# IMU_Section.net
KiCad netlist of a schematic drawn in Altium Designer
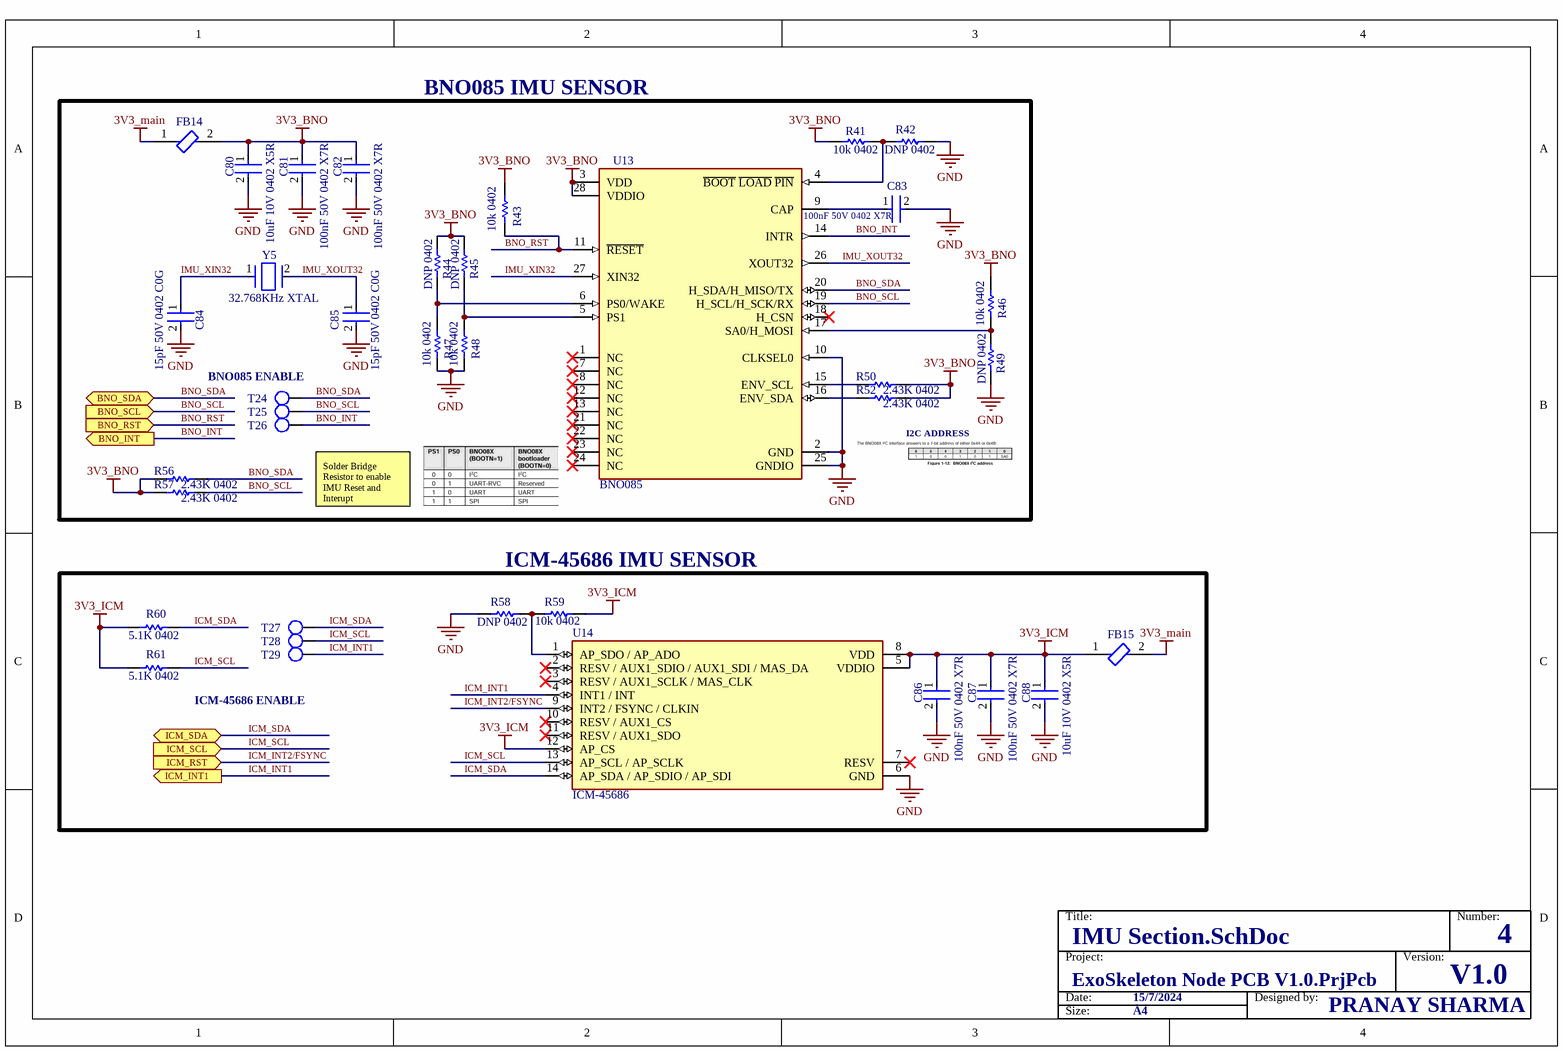
[diagram p0: IMU Section.SchDoc]

(export (version "E")
  (design (tool "Eeschema 10.0.6"))
  (components
    (comp (ref "C80")
      (value "10uF 10V 0402 X5R")
      (footprint "Res, Cap, Ind, LED, FB_Lib:0402 IPC CLASS C CAPACITOR")
      (libsource (lib "Capacitor_Lib") (part "10uF 10V 0402 X5R"))
    )
    (comp (ref "C81")
      (value "100nF 50V 0402 X7R")
      (footprint "Res, Cap, Ind, LED, FB_Lib:0402 IPC CLASS C CAPACITOR")
      (libsource (lib "Capacitor_Lib") (part "100nF 50V 0402 X7R"))
    )
    (comp (ref "C82")
      (value "100nF 50V 0402 X7R")
      (footprint "Res, Cap, Ind, LED, FB_Lib:0402 IPC CLASS C CAPACITOR")
      (libsource (lib "Capacitor_Lib") (part "100nF 50V 0402 X7R"))
    )
    (comp (ref "C83")
      (value "100nF 50V 0402 X7R")
      (footprint "Res, Cap, Ind, LED, FB_Lib:0402 IPC CLASS C CAPACITOR")
      (libsource (lib "Capacitor_Lib") (part "100nF 50V 0402 X7R"))
    )
    (comp (ref "C84")
      (value "15pF 50V 0402 C0G")
      (footprint "Res, Cap, Ind, LED, FB_Lib:0402 IPC CLASS C CAPACITOR")
      (libsource (lib "Capacitor_Lib") (part "15pF 50V 0402 C0G"))
    )
    (comp (ref "C85")
      (value "15pF 50V 0402 C0G")
      (footprint "Res, Cap, Ind, LED, FB_Lib:0402 IPC CLASS C CAPACITOR")
      (libsource (lib "Capacitor_Lib") (part "15pF 50V 0402 C0G"))
    )
    (comp (ref "C86")
      (value "100nF 50V 0402 X7R")
      (footprint "Res, Cap, Ind, LED, FB_Lib:0402 IPC CLASS C CAPACITOR")
      (libsource (lib "Capacitor_Lib") (part "100nF 50V 0402 X7R"))
    )
    (comp (ref "C87")
      (value "100nF 50V 0402 X7R")
      (footprint "Res, Cap, Ind, LED, FB_Lib:0402 IPC CLASS C CAPACITOR")
      (libsource (lib "Capacitor_Lib") (part "100nF 50V 0402 X7R"))
    )
    (comp (ref "C88")
      (value "10uF 10V 0402 X5R")
      (footprint "Res, Cap, Ind, LED, FB_Lib:0402 IPC CLASS C CAPACITOR")
      (libsource (lib "Capacitor_Lib") (part "10uF 10V 0402 X5R"))
    )
    (comp (ref "FB14")
      (value "BLM15AX102SN1D")
      (footprint "Res, Cap, Ind, LED, FB_Lib:0402 IPC CLASS C FERRITE BEAD")
      (libsource (lib "Ferrite_Bead_Lib") (part "BLM15AX102SN1D"))
    )
    (comp (ref "FB15")
      (value "BLM15AX102SN1D")
      (footprint "Res, Cap, Ind, LED, FB_Lib:0402 IPC CLASS C FERRITE BEAD")
      (libsource (lib "Ferrite_Bead_Lib") (part "BLM15AX102SN1D"))
    )
    (comp (ref "R41")
      (value "10k 0402")
      (footprint "Res, Cap, Ind, LED, FB_Lib:0402 IPC CLASS C RESISTOR")
      (libsource (lib "Resistor_Lib") (part "10k 1% 0402"))
    )
    (comp (ref "R42")
      (value "DNP 0402")
      (footprint "Res, Cap, Ind, LED, FB_Lib:0402 IPC CLASS C RESISTOR")
      (libsource (lib "Resistor_Lib") (part "0R 1% 0402"))
    )
    (comp (ref "R43")
      (value "10k 0402")
      (footprint "Res, Cap, Ind, LED, FB_Lib:0402 IPC CLASS C RESISTOR")
      (libsource (lib "Resistor_Lib") (part "10k 1% 0402"))
    )
    (comp (ref "R44")
      (value "DNP 0402")
      (footprint "Res, Cap, Ind, LED, FB_Lib:0402 IPC CLASS C RESISTOR")
      (libsource (lib "Resistor_Lib") (part "0R 1% 0402"))
    )
    (comp (ref "R45")
      (value "DNP 0402")
      (footprint "Res, Cap, Ind, LED, FB_Lib:0402 IPC CLASS C RESISTOR")
      (libsource (lib "Resistor_Lib") (part "0R 1% 0402"))
    )
    (comp (ref "R46")
      (value "10k 0402")
      (footprint "Res, Cap, Ind, LED, FB_Lib:0402 IPC CLASS C RESISTOR")
      (libsource (lib "Resistor_Lib") (part "10k 1% 0402"))
    )
    (comp (ref "R47")
      (value "10k 0402")
      (footprint "Res, Cap, Ind, LED, FB_Lib:0402 IPC CLASS C RESISTOR")
      (libsource (lib "Resistor_Lib") (part "10k 1% 0402"))
    )
    (comp (ref "R48")
      (value "10k 0402")
      (footprint "Res, Cap, Ind, LED, FB_Lib:0402 IPC CLASS C RESISTOR")
      (libsource (lib "Resistor_Lib") (part "10k 1% 0402"))
    )
    (comp (ref "R49")
      (value "DNP 0402")
      (footprint "Res, Cap, Ind, LED, FB_Lib:0402 IPC CLASS C RESISTOR")
      (libsource (lib "Resistor_Lib") (part "0R 1% 0402"))
    )
    (comp (ref "R50")
      (value "2.43K 0402")
      (footprint "Res, Cap, Ind, LED, FB_Lib:0402 IPC CLASS C RESISTOR")
      (libsource (lib "Resistor_Lib") (part "2.43K 1% 0402"))
    )
    (comp (ref "R52")
      (value "2.43K 0402")
      (footprint "Res, Cap, Ind, LED, FB_Lib:0402 IPC CLASS C RESISTOR")
      (libsource (lib "Resistor_Lib") (part "2.43K 1% 0402"))
    )
    (comp (ref "R56")
      (value "2.43K 0402")
      (footprint "Res, Cap, Ind, LED, FB_Lib:0402 IPC CLASS C RESISTOR")
      (libsource (lib "Resistor_Lib") (part "2.43K 1% 0402"))
    )
    (comp (ref "R57")
      (value "2.43K 0402")
      (footprint "Res, Cap, Ind, LED, FB_Lib:0402 IPC CLASS C RESISTOR")
      (libsource (lib "Resistor_Lib") (part "2.43K 1% 0402"))
    )
    (comp (ref "R58")
      (value "DNP 0402")
      (footprint "Res, Cap, Ind, LED, FB_Lib:0402 IPC CLASS C RESISTOR")
      (libsource (lib "Resistor_Lib") (part "0R 1% 0402"))
    )
    (comp (ref "R59")
      (value "10k 0402")
      (footprint "Res, Cap, Ind, LED, FB_Lib:0402 IPC CLASS C RESISTOR")
      (libsource (lib "Resistor_Lib") (part "10k 1% 0402"))
    )
    (comp (ref "R60")
      (value "5.1K 0402")
      (footprint "Res, Cap, Ind, LED, FB_Lib:0402 IPC CLASS C RESISTOR")
      (libsource (lib "Resistor_Lib") (part "5.1K 1% 0402"))
    )
    (comp (ref "R61")
      (value "5.1K 0402")
      (footprint "Res, Cap, Ind, LED, FB_Lib:0402 IPC CLASS C RESISTOR")
      (libsource (lib "Resistor_Lib") (part "5.1K 1% 0402"))
    )
    (comp (ref "T24")
      (value "TP")
      (footprint "Miscellaneous_Lib:Testpoint1")
      (libsource (lib "Miscellaneous_Lib") (part "Testpoint1"))
    )
    (comp (ref "T25")
      (value "TP")
      (footprint "Miscellaneous_Lib:Testpoint1")
      (libsource (lib "Miscellaneous_Lib") (part "Testpoint1"))
    )
    (comp (ref "T26")
      (value "TP")
      (footprint "Miscellaneous_Lib:Testpoint1")
      (libsource (lib "Miscellaneous_Lib") (part "Testpoint1"))
    )
    (comp (ref "T27")
      (value "TP")
      (footprint "Miscellaneous_Lib:Testpoint1")
      (libsource (lib "Miscellaneous_Lib") (part "Testpoint1"))
    )
    (comp (ref "T28")
      (value "TP")
      (footprint "Miscellaneous_Lib:Testpoint1")
      (libsource (lib "Miscellaneous_Lib") (part "Testpoint1"))
    )
    (comp (ref "T29")
      (value "TP")
      (footprint "Miscellaneous_Lib:Testpoint1")
      (libsource (lib "Miscellaneous_Lib") (part "Testpoint1"))
    )
    (comp (ref "U13")
      (value "BNO085")
      (footprint "Integrated_Circuits_Lib:LGA-28 BNO055 IPC-C")
      (libsource (lib "Integrated_Circuits_Lib") (part "BNO085"))
    )
    (comp (ref "U14")
      (value "ICM-45686")
      (footprint "Integrated_Circuits_Lib:LGA-14 ICM-45686 IPC-C")
      (libsource (lib "Integrated_Circuits_Lib") (part "ICM-45686"))
    )
    (comp (ref "Y5")
      (value "32.768KHz XTAL")
      (footprint "Crystals_and_Oscillators_Lib:SMD3215-2P IPC-C")
      (libsource (lib "Crystals_and_Oscillators_Lib") (part "H31003271C2070CY"))
    )
  )
  (nets
    (net (code "1") (name "/BNO_INT") (class "Default")
      (node (ref "T26") (pin "0") (pinfunction "0_0") (pintype "passive"))
      (node (ref "U13") (pin "14") (pinfunction "INTR_14") (pintype "output"))
    )
    (net (code "2") (name "/BNO_RST") (class "Default")
      (node (ref "R43") (pin "1") (pinfunction "1_1") (pintype "passive"))
      (node (ref "U13") (pin "11") (pinfunction "~{RESET}_11") (pintype "input"))
    )
    (net (code "3") (name "/BNO_SCL") (class "Default")
      (node (ref "R57") (pin "2") (pinfunction "2_2") (pintype "passive"))
      (node (ref "T25") (pin "0") (pinfunction "0_0") (pintype "passive"))
      (node (ref "U13") (pin "19") (pinfunction "H_SCL/H_SCK/RX_19") (pintype "bidirectional"))
    )
    (net (code "4") (name "/BNO_SDA") (class "Default")
      (node (ref "R56") (pin "2") (pinfunction "2_2") (pintype "passive"))
      (node (ref "T24") (pin "0") (pinfunction "0_0") (pintype "passive"))
      (node (ref "U13") (pin "20") (pinfunction "H_SDA/H_MISO/TX_20") (pintype "bidirectional"))
    )
    (net (code "5") (name "/ICM_INT1") (class "Default")
      (node (ref "T29") (pin "0") (pinfunction "0_0") (pintype "passive"))
      (node (ref "U14") (pin "4") (pinfunction "INT1_/_INT_4") (pintype "bidirectional"))
    )
    (net (code "6") (name "/ICM_INT2{slash}FSYNC") (class "Default")
      (node (ref "U14") (pin "9") (pinfunction "INT2_/_FSYNC_/_CLKIN_9") (pintype "bidirectional"))
    )
    (net (code "7") (name "/ICM_SCL") (class "Default")
      (node (ref "R61") (pin "2") (pinfunction "2_2") (pintype "passive"))
      (node (ref "T28") (pin "0") (pinfunction "0_0") (pintype "passive"))
      (node (ref "U14") (pin "13") (pinfunction "AP_SCL_/_AP_SCLK_13") (pintype "bidirectional"))
    )
    (net (code "8") (name "/ICM_SDA") (class "Default")
      (node (ref "R60") (pin "2") (pinfunction "2_2") (pintype "passive"))
      (node (ref "T27") (pin "0") (pinfunction "0_0") (pintype "passive"))
      (node (ref "U14") (pin "14") (pinfunction "AP_SDA_/_AP_SDIO_/_AP_SDI_14") (pintype "bidirectional"))
    )
    (net (code "9") (name "/IMU_XIN32") (class "Default")
      (node (ref "C84") (pin "1") (pinfunction "1_1") (pintype "passive"))
      (node (ref "U13") (pin "27") (pinfunction "XIN32_27") (pintype "input"))
      (node (ref "Y5") (pin "1") (pinfunction "1_1") (pintype "passive"))
    )
    (net (code "10") (name "/IMU_XOUT32") (class "Default")
      (node (ref "C85") (pin "1") (pinfunction "1_1") (pintype "passive"))
      (node (ref "U13") (pin "26") (pinfunction "XOUT32_26") (pintype "output"))
      (node (ref "Y5") (pin "2") (pinfunction "2_2") (pintype "passive"))
    )
    (net (code "11") (name "3V3_BNO") (class "Default")
      (node (ref "C80") (pin "1") (pinfunction "1_1") (pintype "passive"))
      (node (ref "C81") (pin "1") (pinfunction "1_1") (pintype "passive"))
      (node (ref "C82") (pin "1") (pinfunction "1_1") (pintype "passive"))
      (node (ref "FB14") (pin "2") (pinfunction "2_2") (pintype "passive"))
      (node (ref "R41") (pin "1") (pinfunction "1_1") (pintype "passive"))
      (node (ref "R43") (pin "2") (pinfunction "2_2") (pintype "passive"))
      (node (ref "R44") (pin "2") (pinfunction "2_2") (pintype "passive"))
      (node (ref "R45") (pin "2") (pinfunction "2_2") (pintype "passive"))
      (node (ref "R46") (pin "2") (pinfunction "2_2") (pintype "passive"))
      (node (ref "R50") (pin "2") (pinfunction "2_2") (pintype "passive"))
      (node (ref "R52") (pin "2") (pinfunction "2_2") (pintype "passive"))
      (node (ref "R56") (pin "1") (pinfunction "1_1") (pintype "passive"))
      (node (ref "R57") (pin "1") (pinfunction "1_1") (pintype "passive"))
      (node (ref "U13") (pin "28") (pinfunction "VDDIO_28") (pintype "power_in"))
      (node (ref "U13") (pin "3") (pinfunction "VDD_3") (pintype "power_in"))
    )
    (net (code "12") (name "3V3_ICM") (class "Default")
      (node (ref "C86") (pin "1") (pinfunction "1_1") (pintype "passive"))
      (node (ref "C87") (pin "1") (pinfunction "1_1") (pintype "passive"))
      (node (ref "C88") (pin "1") (pinfunction "1_1") (pintype "passive"))
      (node (ref "FB15") (pin "1") (pinfunction "1_1") (pintype "passive"))
      (node (ref "R59") (pin "1") (pinfunction "1_1") (pintype "passive"))
      (node (ref "R60") (pin "1") (pinfunction "1_1") (pintype "passive"))
      (node (ref "R61") (pin "1") (pinfunction "1_1") (pintype "passive"))
      (node (ref "U14") (pin "12") (pinfunction "AP_CS_12") (pintype "bidirectional"))
      (node (ref "U14") (pin "5") (pinfunction "VDDIO_5") (pintype "power_in"))
      (node (ref "U14") (pin "8") (pinfunction "VDD_8") (pintype "power_in"))
    )
    (net (code "13") (name "3V3_main") (class "Default")
      (node (ref "FB14") (pin "1") (pinfunction "1_1") (pintype "passive"))
      (node (ref "FB15") (pin "2") (pinfunction "2_2") (pintype "passive"))
    )
    (net (code "14") (name "GND") (class "Default")
      (node (ref "C80") (pin "2") (pinfunction "2_2") (pintype "passive"))
      (node (ref "C81") (pin "2") (pinfunction "2_2") (pintype "passive"))
      (node (ref "C82") (pin "2") (pinfunction "2_2") (pintype "passive"))
      (node (ref "C83") (pin "2") (pinfunction "2_2") (pintype "passive"))
      (node (ref "C84") (pin "2") (pinfunction "2_2") (pintype "passive"))
      (node (ref "C85") (pin "2") (pinfunction "2_2") (pintype "passive"))
      (node (ref "C86") (pin "2") (pinfunction "2_2") (pintype "passive"))
      (node (ref "C87") (pin "2") (pinfunction "2_2") (pintype "passive"))
      (node (ref "C88") (pin "2") (pinfunction "2_2") (pintype "passive"))
      (node (ref "R42") (pin "1") (pinfunction "1_1") (pintype "passive"))
      (node (ref "R47") (pin "1") (pinfunction "1_1") (pintype "passive"))
      (node (ref "R48") (pin "1") (pinfunction "1_1") (pintype "passive"))
      (node (ref "R49") (pin "1") (pinfunction "1_1") (pintype "passive"))
      (node (ref "R58") (pin "2") (pinfunction "2_2") (pintype "passive"))
      (node (ref "U13") (pin "10") (pinfunction "CLKSEL0_10") (pintype "input"))
      (node (ref "U13") (pin "2") (pinfunction "GND_2") (pintype "power_in"))
      (node (ref "U13") (pin "25") (pinfunction "GNDIO_25") (pintype "power_in"))
      (node (ref "U14") (pin "6") (pinfunction "GND_6") (pintype "power_in"))
    )
    (net (code "15") (name "Net-(U13-CAP)") (class "Default")
      (node (ref "C83") (pin "1") (pinfunction "1_1") (pintype "passive"))
      (node (ref "U13") (pin "9") (pinfunction "CAP_9") (pintype "power_in"))
    )
    (net (code "16") (name "Net-(U13-ENV_SCL)") (class "Default")
      (node (ref "R50") (pin "1") (pinfunction "1_1") (pintype "passive"))
      (node (ref "U13") (pin "15") (pinfunction "ENV_SCL_15") (pintype "input"))
    )
    (net (code "17") (name "Net-(U13-ENV_SDA)") (class "Default")
      (node (ref "R52") (pin "1") (pinfunction "1_1") (pintype "passive"))
      (node (ref "U13") (pin "16") (pinfunction "ENV_SDA_16") (pintype "bidirectional"))
    )
    (net (code "18") (name "Net-(U13-PS0{slash}WAKE)") (class "Default")
      (node (ref "R44") (pin "1") (pinfunction "1_1") (pintype "passive"))
      (node (ref "R47") (pin "2") (pinfunction "2_2") (pintype "passive"))
      (node (ref "U13") (pin "6") (pinfunction "PS0/WAKE_6") (pintype "input"))
    )
    (net (code "19") (name "Net-(U13-PS1)") (class "Default")
      (node (ref "R45") (pin "1") (pinfunction "1_1") (pintype "passive"))
      (node (ref "R48") (pin "2") (pinfunction "2_2") (pintype "passive"))
      (node (ref "U13") (pin "5") (pinfunction "PS1_5") (pintype "input"))
    )
    (net (code "20") (name "Net-(U13-SA0{slash}H_MOSI)") (class "Default")
      (node (ref "R46") (pin "1") (pinfunction "1_1") (pintype "passive"))
      (node (ref "R49") (pin "2") (pinfunction "2_2") (pintype "passive"))
      (node (ref "U13") (pin "17") (pinfunction "SA0/H_MOSI_17") (pintype "input"))
    )
    (net (code "21") (name "Net-(U13-~{BOOT}_~{LOAD}_~{PIN})") (class "Default")
      (node (ref "R41") (pin "2") (pinfunction "2_2") (pintype "passive"))
      (node (ref "R42") (pin "2") (pinfunction "2_2") (pintype "passive"))
      (node (ref "U13") (pin "4") (pinfunction "~{BOOT}_~{LOAD}_~{PIN}_4") (pintype "input"))
    )
    (net (code "22") (name "Net-(U14-AP_SDO_{slash}_AP_ADO)") (class "Default")
      (node (ref "R58") (pin "1") (pinfunction "1_1") (pintype "passive"))
      (node (ref "R59") (pin "2") (pinfunction "2_2") (pintype "passive"))
      (node (ref "U14") (pin "1") (pinfunction "AP_SDO_/_AP_ADO_1") (pintype "bidirectional"))
    )
    (net (code "23") (name "unconnected-(U13-H_CSN-Pad18)") (class "Default")
      (node (ref "U13") (pin "18") (pinfunction "H_CSN_18") (pintype "bidirectional+no_connect"))
    )
    (net (code "24") (name "unconnected-(U13-NC-Pad1)") (class "Default")
      (node (ref "U13") (pin "1") (pinfunction "NC_1") (pintype "passive+no_connect"))
    )
    (net (code "25") (name "unconnected-(U13-NC-Pad7)") (class "Default")
      (node (ref "U13") (pin "7") (pinfunction "NC_7") (pintype "passive+no_connect"))
    )
    (net (code "26") (name "unconnected-(U13-NC-Pad8)") (class "Default")
      (node (ref "U13") (pin "8") (pinfunction "NC_8") (pintype "passive+no_connect"))
    )
    (net (code "27") (name "unconnected-(U13-NC-Pad12)") (class "Default")
      (node (ref "U13") (pin "12") (pinfunction "NC_12") (pintype "passive+no_connect"))
    )
    (net (code "28") (name "unconnected-(U13-NC-Pad13)") (class "Default")
      (node (ref "U13") (pin "13") (pinfunction "NC_13") (pintype "passive+no_connect"))
    )
    (net (code "29") (name "unconnected-(U13-NC-Pad21)") (class "Default")
      (node (ref "U13") (pin "21") (pinfunction "NC_21") (pintype "passive+no_connect"))
    )
    (net (code "30") (name "unconnected-(U13-NC-Pad22)") (class "Default")
      (node (ref "U13") (pin "22") (pinfunction "NC_22") (pintype "passive+no_connect"))
    )
    (net (code "31") (name "unconnected-(U13-NC-Pad23)") (class "Default")
      (node (ref "U13") (pin "23") (pinfunction "NC_23") (pintype "passive+no_connect"))
    )
    (net (code "32") (name "unconnected-(U13-NC-Pad24)") (class "Default")
      (node (ref "U13") (pin "24") (pinfunction "NC_24") (pintype "passive+no_connect"))
    )
    (net (code "33") (name "unconnected-(U14-RESV-Pad7)") (class "Default")
      (node (ref "U14") (pin "7") (pinfunction "RESV_7") (pintype "passive+no_connect"))
    )
    (net (code "34") (name "unconnected-(U14-RESV_{slash}_AUX1_CS-Pad10)") (class "Default")
      (node (ref "U14") (pin "10") (pinfunction "RESV_/_AUX1_CS_10") (pintype "bidirectional+no_connect"))
    )
    (net (code "35") (name "unconnected-(U14-RESV_{slash}_AUX1_SCLK_{slash}_MAS_CLK-Pad3)") (class "Default")
      (node (ref "U14") (pin "3") (pinfunction "RESV_/_AUX1_SCLK_/_MAS_CLK_3") (pintype "bidirectional+no_connect"))
    )
    (net (code "36") (name "unconnected-(U14-RESV_{slash}_AUX1_SDIO_{slash}_AUX1_SDI_{slash}_MAS_DA-Pad2)") (class "Default")
      (node (ref "U14") (pin "2") (pinfunction "RESV_/_AUX1_SDIO_/_AUX1_SDI_/_MAS_DA_2") (pintype "bidirectional+no_connect"))
    )
    (net (code "37") (name "unconnected-(U14-RESV_{slash}_AUX1_SDO-Pad11)") (class "Default")
      (node (ref "U14") (pin "11") (pinfunction "RESV_/_AUX1_SDO_11") (pintype "bidirectional+no_connect"))
    )
  )
)
